# Motors.net
KiCad netlist of a schematic drawn in EAGLE
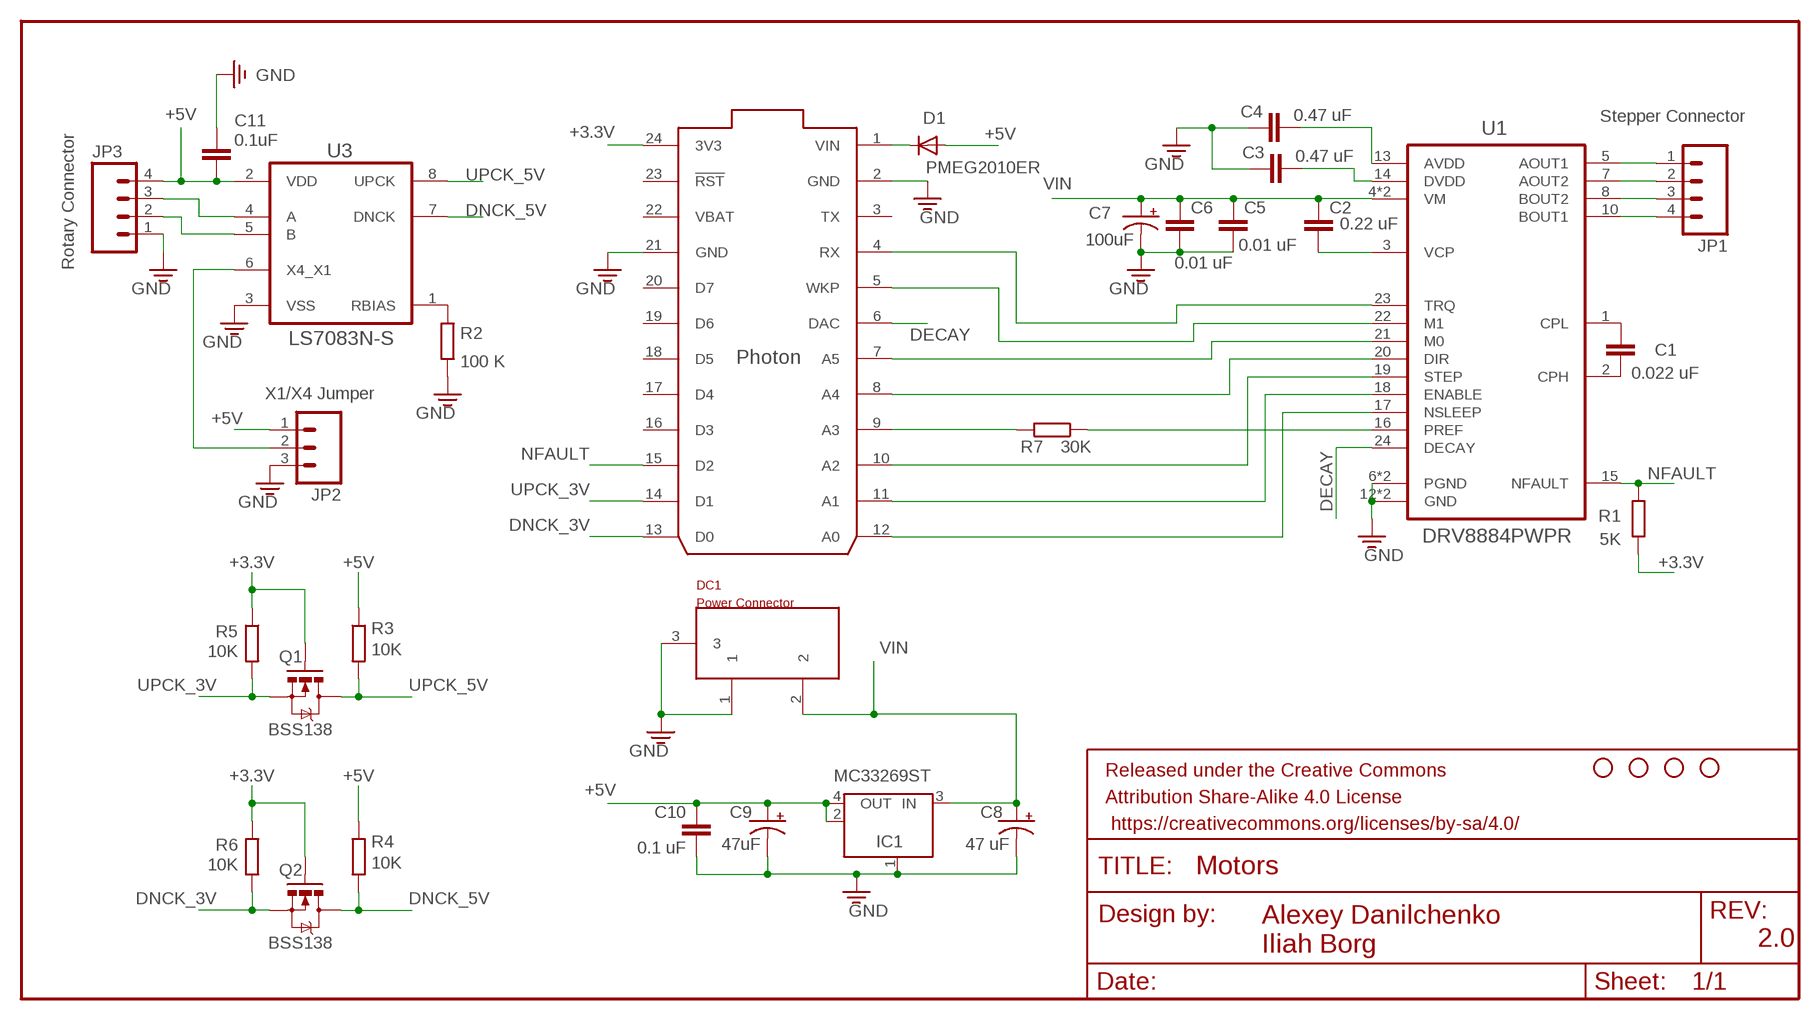
[diagram p0: schematic, sheet 1]

(export (version "E")
  (design (tool "Eeschema 10.0.6"))
  (components
    (comp (ref "C1")
      (value "0.022 uF")
      (footprint "eagle-import:C0805")
      (libsource (lib "eagle-import") (part "C-EUC0805"))
    )
    (comp (ref "C2")
      (value "0.22 uF")
      (footprint "eagle-import:C0805")
      (libsource (lib "eagle-import") (part "C-EUC0805"))
    )
    (comp (ref "C3")
      (value "0.47 uF")
      (footprint "eagle-import:C0805")
      (libsource (lib "eagle-import") (part "C-EUC0805"))
    )
    (comp (ref "C4")
      (value "0.47 uF")
      (footprint "eagle-import:C0805")
      (libsource (lib "eagle-import") (part "C-EUC0805"))
    )
    (comp (ref "C5")
      (value "0.01 uF")
      (footprint "eagle-import:C0805")
      (libsource (lib "eagle-import") (part "C-EUC0805"))
    )
    (comp (ref "C6")
      (value "0.01 uF")
      (footprint "eagle-import:C0805")
      (libsource (lib "eagle-import") (part "C-EUC0805"))
    )
    (comp (ref "C7")
      (value "100uF")
      (footprint "eagle-import:CT7343")
      (libsource (lib "eagle-import") (part "CPOL-USCT7343"))
    )
    (comp (ref "C8")
      (value "47 uF")
      (footprint "eagle-import:CT7343")
      (libsource (lib "eagle-import") (part "CPOL-USCT7343"))
    )
    (comp (ref "C9")
      (value "47uF")
      (footprint "eagle-import:CT7343")
      (libsource (lib "eagle-import") (part "CPOL-USCT7343"))
    )
    (comp (ref "C10")
      (value "0.1 uF")
      (footprint "eagle-import:C0805")
      (libsource (lib "eagle-import") (part "C-EUC0805"))
    )
    (comp (ref "C11")
      (value "0.1uF")
      (footprint "eagle-import:C0805")
      (libsource (lib "eagle-import") (part "C-EUC0805"))
    )
    (comp (ref "D1")
      (value "PMEG2010ER")
      (footprint "eagle-import:SOD123")
      (libsource (lib "eagle-import") (part "DIODE-SOD123"))
    )
    (comp (ref "DC1")
      (value "Power Connector")
      (footprint "eagle-import:POWERSUPPLY_DC-21MM")
      (libsource (lib "eagle-import") (part "POWERSUPPLY_DC21MMX"))
    )
    (comp (ref "FRAME1")
      (value "FRAME-LETTER")
      (footprint "eagle-import:CREATIVE_COMMONS")
      (libsource (lib "eagle-import") (part "FRAME-LETTER"))
    )
    (comp (ref "IC1")
      (value "MC33269ST")
      (footprint "eagle-import:SOT223")
      (libsource (lib "eagle-import") (part "MC33269ST"))
    )
    (comp (ref "JP1")
      (value "Stepper Connector")
      (footprint "eagle-import:1X04")
      (libsource (lib "eagle-import") (part "M04PTH"))
    )
    (comp (ref "JP2")
      (value "X1/X4 Jumper")
      (footprint "eagle-import:1X03")
      (libsource (lib "eagle-import") (part "M03PTH"))
    )
    (comp (ref "JP3")
      (value "Rotary Connector")
      (footprint "eagle-import:1X04")
      (libsource (lib "eagle-import") (part "M04PTH"))
    )
    (comp (ref "Q1")
      (value "BSS138")
      (footprint "eagle-import:SOT23-3")
      (libsource (lib "eagle-import") (part "MOSFET-NCHANNELSMD"))
    )
    (comp (ref "Q2")
      (value "BSS138")
      (footprint "eagle-import:SOT23-3")
      (libsource (lib "eagle-import") (part "MOSFET-NCHANNELSMD"))
    )
    (comp (ref "R1")
      (value "5K")
      (footprint "eagle-import:R0805")
      (libsource (lib "eagle-import") (part "R-EU_R0805"))
    )
    (comp (ref "R2")
      (value "100 K")
      (footprint "eagle-import:R0805")
      (libsource (lib "eagle-import") (part "R-EU_R0805"))
    )
    (comp (ref "R3")
      (value "10K")
      (footprint "eagle-import:R0805")
      (libsource (lib "eagle-import") (part "R-EU_R0805"))
    )
    (comp (ref "R4")
      (value "10K")
      (footprint "eagle-import:R0805")
      (libsource (lib "eagle-import") (part "R-EU_R0805"))
    )
    (comp (ref "R5")
      (value "10K")
      (footprint "eagle-import:R0805")
      (libsource (lib "eagle-import") (part "R-EU_R0805"))
    )
    (comp (ref "R6")
      (value "10K")
      (footprint "eagle-import:R0805")
      (libsource (lib "eagle-import") (part "R-EU_R0805"))
    )
    (comp (ref "R7")
      (value "30K")
      (footprint "eagle-import:R0805")
      (libsource (lib "eagle-import") (part "R-EU_R0805"))
    )
    (comp (ref "STANDOFF1")
      (value "STAND-OFF")
      (footprint "eagle-import:STAND-OFF")
      (libsource (lib "eagle-import") (part "STAND-OFF"))
    )
    (comp (ref "STANDOFF2")
      (value "STAND-OFF")
      (footprint "eagle-import:STAND-OFF")
      (libsource (lib "eagle-import") (part "STAND-OFF"))
    )
    (comp (ref "STANDOFF3")
      (value "STAND-OFF")
      (footprint "eagle-import:STAND-OFF")
      (libsource (lib "eagle-import") (part "STAND-OFF"))
    )
    (comp (ref "STANDOFF4")
      (value "STAND-OFF")
      (footprint "eagle-import:STAND-OFF")
      (libsource (lib "eagle-import") (part "STAND-OFF"))
    )
    (comp (ref "U1")
      (value "DRV8884PWPR")
      (footprint "eagle-import:SOP65P640X120-29N")
      (libsource (lib "eagle-import") (part "DRV8884PWPR"))
    )
    (comp (ref "U2")
      (value "PHOTON_WITH_HEADERS")
      (footprint "eagle-import:PHOTON")
      (libsource (lib "eagle-import") (part "PHOTON_WITH_HEADERS"))
    )
    (comp (ref "U3")
      (value "LS7083N-S")
      (footprint "eagle-import:SOIC127P600X175-8N")
      (libsource (lib "eagle-import") (part "LSI7083N-S"))
    )
  )
  (nets
    (net (code "1") (name "/+3.3V") (class "Default")
      (node (ref "Q1") (pin "1") (pinfunction "G_1") (pintype "passive"))
      (node (ref "Q2") (pin "1") (pinfunction "G_1") (pintype "passive"))
      (node (ref "R1") (pin "1") (pinfunction "1_1") (pintype "passive"))
      (node (ref "R5") (pin "1") (pinfunction "1_1") (pintype "passive"))
      (node (ref "R6") (pin "1") (pinfunction "1_1") (pintype "passive"))
      (node (ref "U2") (pin "24") (pinfunction "3V3_24") (pintype "power_in"))
    )
    (net (code "2") (name "/+5V") (class "Default")
      (node (ref "C10") (pin "1") (pinfunction "1_1") (pintype "passive"))
      (node (ref "C11") (pin "2") (pinfunction "2_2") (pintype "passive"))
      (node (ref "C9") (pin "+") (pinfunction "+_+") (pintype "passive"))
      (node (ref "D1") (pin "A") (pinfunction "A_A") (pintype "passive"))
      (node (ref "IC1") (pin "2") (pinfunction "OUT_2") (pintype "passive"))
      (node (ref "IC1") (pin "4") (pinfunction "OUT_4") (pintype "passive"))
      (node (ref "JP2") (pin "1") (pinfunction "1_1") (pintype "passive"))
      (node (ref "JP3") (pin "4") (pinfunction "4_4") (pintype "passive"))
      (node (ref "R3") (pin "1") (pinfunction "1_1") (pintype "passive"))
      (node (ref "R4") (pin "1") (pinfunction "1_1") (pintype "passive"))
      (node (ref "U3") (pin "2") (pinfunction "VDD_2") (pintype "power_in"))
    )
    (net (code "3") (name "/DECAY") (class "Default")
      (node (ref "U1") (pin "24") (pinfunction "DECAY_24") (pintype "input"))
      (node (ref "U2") (pin "6") (pinfunction "DAC_6") (pintype "bidirectional"))
    )
    (net (code "4") (name "/DNCK_3V") (class "Default")
      (node (ref "Q2") (pin "2") (pinfunction "S_2") (pintype "passive"))
      (node (ref "R6") (pin "2") (pinfunction "2_2") (pintype "passive"))
      (node (ref "U2") (pin "13") (pinfunction "D0_13") (pintype "bidirectional"))
    )
    (net (code "5") (name "/DNCK_5V") (class "Default")
      (node (ref "Q2") (pin "3") (pinfunction "D_3") (pintype "passive"))
      (node (ref "R4") (pin "2") (pinfunction "2_2") (pintype "passive"))
      (node (ref "U3") (pin "7") (pinfunction "DNCK_7") (pintype "output"))
    )
    (net (code "6") (name "/NFAULT") (class "Default")
      (node (ref "R1") (pin "2") (pinfunction "2_2") (pintype "passive"))
      (node (ref "U1") (pin "15") (pinfunction "NFAULT_15") (pintype "output"))
      (node (ref "U2") (pin "15") (pinfunction "D2_15") (pintype "bidirectional"))
    )
    (net (code "7") (name "/UPCK_3V") (class "Default")
      (node (ref "Q1") (pin "2") (pinfunction "S_2") (pintype "passive"))
      (node (ref "R5") (pin "2") (pinfunction "2_2") (pintype "passive"))
      (node (ref "U2") (pin "14") (pinfunction "D1_14") (pintype "bidirectional"))
    )
    (net (code "8") (name "/UPCK_5V") (class "Default")
      (node (ref "Q1") (pin "3") (pinfunction "D_3") (pintype "passive"))
      (node (ref "R3") (pin "2") (pinfunction "2_2") (pintype "passive"))
      (node (ref "U3") (pin "8") (pinfunction "UPCK_8") (pintype "output"))
    )
    (net (code "9") (name "/VBAT") (class "Default")
      (node (ref "U2") (pin "22") (pinfunction "VBAT_22") (pintype "power_in"))
    )
    (net (code "10") (name "/VIN") (class "Default")
      (node (ref "C2") (pin "1") (pinfunction "1_1") (pintype "passive"))
      (node (ref "C5") (pin "1") (pinfunction "1_1") (pintype "passive"))
      (node (ref "C6") (pin "1") (pinfunction "1_1") (pintype "passive"))
      (node (ref "C7") (pin "+") (pinfunction "+_+") (pintype "passive"))
      (node (ref "C8") (pin "+") (pinfunction "+_+") (pintype "passive"))
      (node (ref "DC1") (pin "2") (pinfunction "2_2") (pintype "power_in"))
      (node (ref "IC1") (pin "3") (pinfunction "IN_3") (pintype "input"))
      (node (ref "U1") (pin "11") (pinfunction "VM_11") (pintype "power_in"))
      (node (ref "U1") (pin "4") (pinfunction "VM_4") (pintype "power_in"))
    )
    (net (code "11") (name "GND") (class "Default")
      (node (ref "C10") (pin "2") (pinfunction "2_2") (pintype "passive"))
      (node (ref "C11") (pin "1") (pinfunction "1_1") (pintype "passive"))
      (node (ref "C3") (pin "2") (pinfunction "2_2") (pintype "passive"))
      (node (ref "C4") (pin "2") (pinfunction "2_2") (pintype "passive"))
      (node (ref "C5") (pin "2") (pinfunction "2_2") (pintype "passive"))
      (node (ref "C6") (pin "2") (pinfunction "2_2") (pintype "passive"))
      (node (ref "C7") (pin "-") (pinfunction "-_-") (pintype "passive"))
      (node (ref "C8") (pin "-") (pinfunction "-_-") (pintype "passive"))
      (node (ref "C9") (pin "-") (pinfunction "-_-") (pintype "passive"))
      (node (ref "DC1") (pin "1") (pinfunction "1_1") (pintype "power_in"))
      (node (ref "DC1") (pin "3") (pinfunction "3_3") (pintype "power_in"))
      (node (ref "IC1") (pin "1") (pinfunction "GND/ADJ_1") (pintype "input"))
      (node (ref "JP2") (pin "3") (pinfunction "3_3") (pintype "passive"))
      (node (ref "JP3") (pin "1") (pinfunction "1_1") (pintype "passive"))
      (node (ref "R2") (pin "2") (pinfunction "2_2") (pintype "passive"))
      (node (ref "U1") (pin "12") (pinfunction "GND_12") (pintype "passive"))
      (node (ref "U1") (pin "25") (pinfunction "GND_25") (pintype "passive"))
      (node (ref "U1") (pin "6") (pinfunction "PGND_6") (pintype "passive"))
      (node (ref "U1") (pin "9") (pinfunction "PGND_9") (pintype "passive"))
      (node (ref "U2") (pin "2") (pinfunction "GND_2") (pintype "power_in"))
      (node (ref "U2") (pin "21") (pinfunction "GND_21") (pintype "power_in"))
      (node (ref "U3") (pin "3") (pinfunction "VSS_3") (pintype "power_in"))
    )
    (net (code "12") (name "Net-(U1-AOUT1)") (class "Default")
      (node (ref "JP1") (pin "1") (pinfunction "1_1") (pintype "passive"))
      (node (ref "U1") (pin "5") (pinfunction "AOUT1_5") (pintype "output"))
    )
    (net (code "13") (name "Net-(U1-AOUT2)") (class "Default")
      (node (ref "JP1") (pin "2") (pinfunction "2_2") (pintype "passive"))
      (node (ref "U1") (pin "7") (pinfunction "AOUT2_7") (pintype "output"))
    )
    (net (code "14") (name "Net-(U1-AVDD)") (class "Default")
      (node (ref "C4") (pin "1") (pinfunction "1_1") (pintype "passive"))
      (node (ref "U1") (pin "13") (pinfunction "AVDD_13") (pintype "power_in"))
    )
    (net (code "15") (name "Net-(U1-BOUT1)") (class "Default")
      (node (ref "JP1") (pin "4") (pinfunction "4_4") (pintype "passive"))
      (node (ref "U1") (pin "10") (pinfunction "BOUT1_10") (pintype "output"))
    )
    (net (code "16") (name "Net-(U1-BOUT2)") (class "Default")
      (node (ref "JP1") (pin "3") (pinfunction "3_3") (pintype "passive"))
      (node (ref "U1") (pin "8") (pinfunction "BOUT2_8") (pintype "output"))
    )
    (net (code "17") (name "Net-(U1-CPH)") (class "Default")
      (node (ref "C1") (pin "1") (pinfunction "1_1") (pintype "passive"))
      (node (ref "U1") (pin "2") (pinfunction "CPH_2") (pintype "input"))
    )
    (net (code "18") (name "Net-(U1-CPL)") (class "Default")
      (node (ref "C1") (pin "2") (pinfunction "2_2") (pintype "passive"))
      (node (ref "U1") (pin "1") (pinfunction "CPL_1") (pintype "input"))
    )
    (net (code "19") (name "Net-(U1-DIR)") (class "Default")
      (node (ref "U1") (pin "20") (pinfunction "DIR_20") (pintype "input"))
      (node (ref "U2") (pin "8") (pinfunction "A4_8") (pintype "bidirectional"))
    )
    (net (code "20") (name "Net-(U1-DVDD)") (class "Default")
      (node (ref "C3") (pin "1") (pinfunction "1_1") (pintype "passive"))
      (node (ref "U1") (pin "14") (pinfunction "DVDD_14") (pintype "power_in"))
    )
    (net (code "21") (name "Net-(U1-ENABLE)") (class "Default")
      (node (ref "U1") (pin "18") (pinfunction "ENABLE_18") (pintype "input"))
      (node (ref "U2") (pin "11") (pinfunction "A1_11") (pintype "bidirectional"))
    )
    (net (code "22") (name "Net-(U1-M0)") (class "Default")
      (node (ref "U1") (pin "21") (pinfunction "M0_21") (pintype "input"))
      (node (ref "U2") (pin "7") (pinfunction "A5_7") (pintype "bidirectional"))
    )
    (net (code "23") (name "Net-(U1-M1)") (class "Default")
      (node (ref "U1") (pin "22") (pinfunction "M1_22") (pintype "input"))
      (node (ref "U2") (pin "5") (pinfunction "WKP_5") (pintype "bidirectional"))
    )
    (net (code "24") (name "Net-(U1-NSLEEP)") (class "Default")
      (node (ref "U1") (pin "17") (pinfunction "NSLEEP_17") (pintype "input"))
      (node (ref "U2") (pin "12") (pinfunction "A0_12") (pintype "bidirectional"))
    )
    (net (code "25") (name "Net-(U1-PREF)") (class "Default")
      (node (ref "R7") (pin "1") (pinfunction "1_1") (pintype "passive"))
      (node (ref "U1") (pin "16") (pinfunction "PREF_16") (pintype "input"))
    )
    (net (code "26") (name "Net-(U1-STEP)") (class "Default")
      (node (ref "U1") (pin "19") (pinfunction "STEP_19") (pintype "input"))
      (node (ref "U2") (pin "10") (pinfunction "A2_10") (pintype "bidirectional"))
    )
    (net (code "27") (name "Net-(U1-TRQ)") (class "Default")
      (node (ref "U1") (pin "23") (pinfunction "TRQ_23") (pintype "input"))
      (node (ref "U2") (pin "4") (pinfunction "RX_4") (pintype "bidirectional"))
    )
    (net (code "28") (name "Net-(U1-VCP)") (class "Default")
      (node (ref "C2") (pin "2") (pinfunction "2_2") (pintype "passive"))
      (node (ref "U1") (pin "3") (pinfunction "VCP_3") (pintype "input"))
    )
    (net (code "29") (name "Net-(U2-A3)") (class "Default")
      (node (ref "R7") (pin "2") (pinfunction "2_2") (pintype "passive"))
      (node (ref "U2") (pin "9") (pinfunction "A3_9") (pintype "bidirectional"))
    )
    (net (code "30") (name "Net-(U2-VIN)") (class "Default")
      (node (ref "D1") (pin "C") (pinfunction "C_C") (pintype "passive"))
      (node (ref "U2") (pin "1") (pinfunction "VIN_1") (pintype "power_in"))
    )
    (net (code "31") (name "Net-(U3-A)") (class "Default")
      (node (ref "JP3") (pin "3") (pinfunction "3_3") (pintype "passive"))
      (node (ref "U3") (pin "4") (pinfunction "A_4") (pintype "input"))
    )
    (net (code "32") (name "Net-(U3-B)") (class "Default")
      (node (ref "JP3") (pin "2") (pinfunction "2_2") (pintype "passive"))
      (node (ref "U3") (pin "5") (pinfunction "B_5") (pintype "input"))
    )
    (net (code "33") (name "Net-(U3-RBIAS)") (class "Default")
      (node (ref "R2") (pin "1") (pinfunction "1_1") (pintype "passive"))
      (node (ref "U3") (pin "1") (pinfunction "RBIAS_1") (pintype "input"))
    )
    (net (code "34") (name "Net-(U3-X4_X1)") (class "Default")
      (node (ref "JP2") (pin "2") (pinfunction "2_2") (pintype "passive"))
      (node (ref "U3") (pin "6") (pinfunction "X4_X1_6") (pintype "input"))
    )
    (net (code "35") (name "unconnected-(U2-D3-Pad16)") (class "Default")
      (node (ref "U2") (pin "16") (pinfunction "D3_16") (pintype "bidirectional"))
    )
    (net (code "36") (name "unconnected-(U2-D4-Pad17)") (class "Default")
      (node (ref "U2") (pin "17") (pinfunction "D4_17") (pintype "bidirectional"))
    )
    (net (code "37") (name "unconnected-(U2-D5-Pad18)") (class "Default")
      (node (ref "U2") (pin "18") (pinfunction "D5_18") (pintype "bidirectional"))
    )
    (net (code "38") (name "unconnected-(U2-D6-Pad19)") (class "Default")
      (node (ref "U2") (pin "19") (pinfunction "D6_19") (pintype "bidirectional"))
    )
    (net (code "39") (name "unconnected-(U2-D7-Pad20)") (class "Default")
      (node (ref "U2") (pin "20") (pinfunction "D7_20") (pintype "bidirectional"))
    )
    (net (code "40") (name "unconnected-(U2-TX-Pad3)") (class "Default")
      (node (ref "U2") (pin "3") (pinfunction "TX_3") (pintype "bidirectional"))
    )
    (net (code "41") (name "unconnected-(U2-~{RST}-Pad23)") (class "Default")
      (node (ref "U2") (pin "23") (pinfunction "~{RST}_23") (pintype "bidirectional"))
    )
  )
)
